# teensyShield4_1b.net
KiCad netlist of a schematic drawn in EAGLE
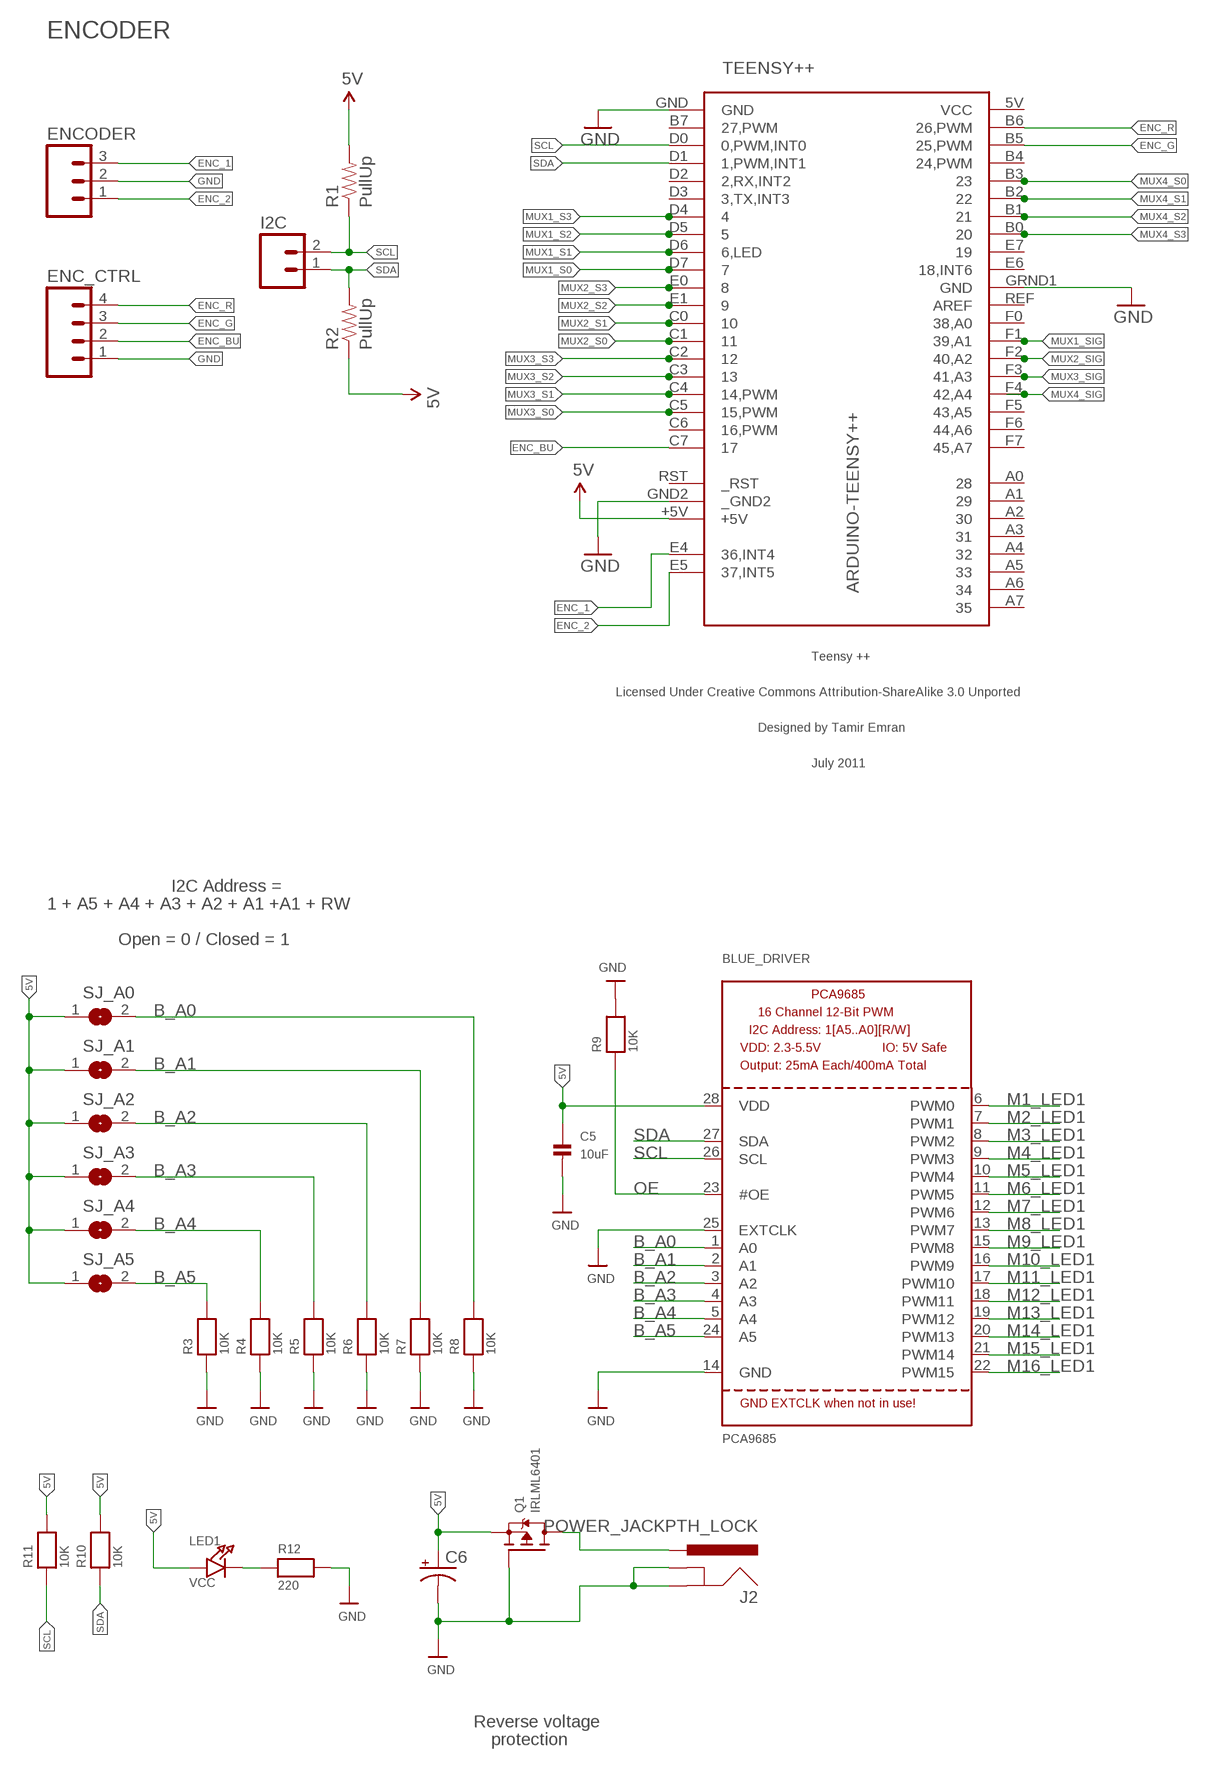
[diagram p0: schematic, sheet 1, part 1 of 2]
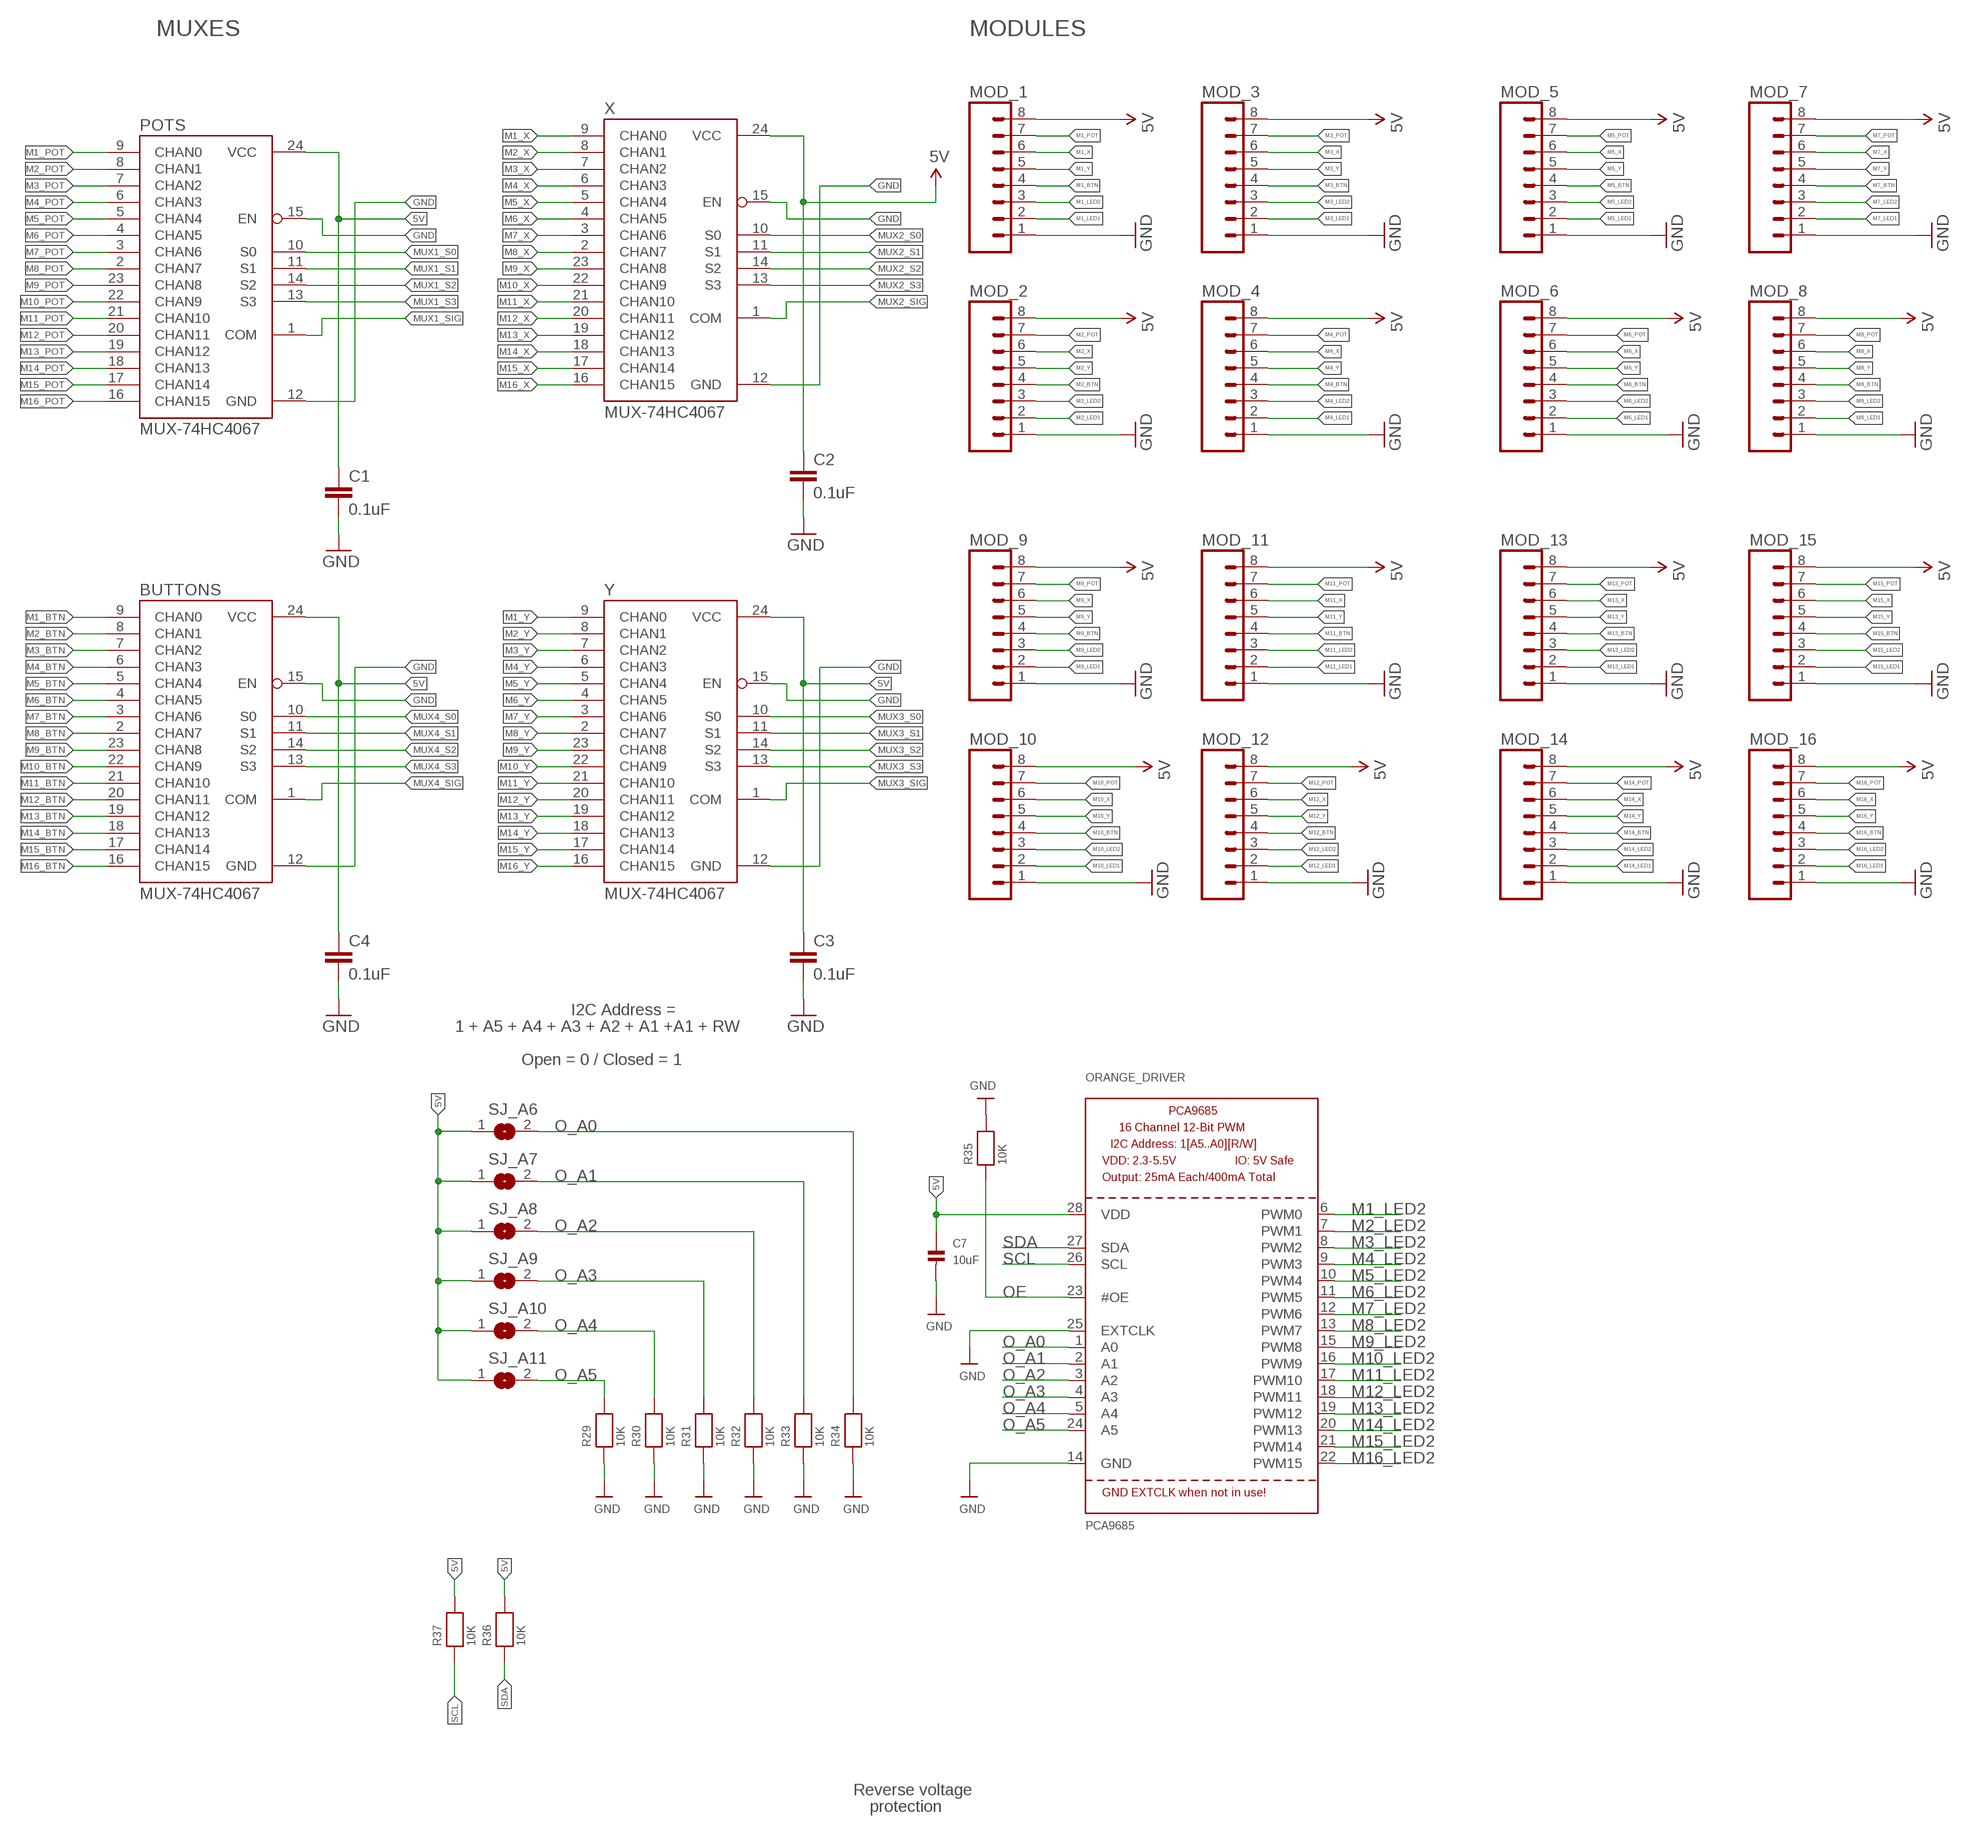
[diagram p1: schematic, sheet 1, part 2 of 2]

(export (version "E")
  (design (tool "Eeschema 10.0.6"))
  (components
    (comp (ref "BLUE_DRIVER")
      (value "PCA9685")
      (footprint "eagle-import:TSSOP28")
      (libsource (lib "eagle-import") (part "PCA9685"))
    )
    (comp (ref "BUTTONS")
      (value "MUX-74HC4067")
      (footprint "eagle-import:SSOP24")
      (libsource (lib "eagle-import") (part "MUX-74HC4067SMD"))
    )
    (comp (ref "C1")
      (value "0.1uF")
      (footprint "eagle-import:0603")
      (libsource (lib "eagle-import") (part "CAP0603"))
    )
    (comp (ref "C2")
      (value "0.1uF")
      (footprint "eagle-import:0603")
      (libsource (lib "eagle-import") (part "CAP0603"))
    )
    (comp (ref "C3")
      (value "0.1uF")
      (footprint "eagle-import:0603")
      (libsource (lib "eagle-import") (part "CAP0603"))
    )
    (comp (ref "C4")
      (value "0.1uF")
      (footprint "eagle-import:0603")
      (libsource (lib "eagle-import") (part "CAP0603"))
    )
    (comp (ref "C5")
      (value "10uF")
      (footprint "eagle-import:0805")
      (libsource (lib "eagle-import") (part "CAP_CERAMIC0805"))
    )
    (comp (ref "C6")
      (value "CPOL-USE3.5-8")
      (footprint "eagle-import:E3,5-8")
      (libsource (lib "eagle-import") (part "CPOL-USE3.5-8"))
    )
    (comp (ref "C7")
      (value "10uF")
      (footprint "eagle-import:0805")
      (libsource (lib "eagle-import") (part "CAP_CERAMIC0805"))
    )
    (comp (ref "ENCODER")
      (value "M031X03_NO_SILK")
      (footprint "eagle-import:1X03_NO_SILK")
      (libsource (lib "eagle-import") (part "M031X03_NO_SILK"))
    )
    (comp (ref "ENC_CTRL")
      (value "M041X04_NO_SILK")
      (footprint "eagle-import:1X04_NO_SILK")
      (libsource (lib "eagle-import") (part "M041X04_NO_SILK"))
    )
    (comp (ref "I2C")
      (value "M02LOCK")
      (footprint "eagle-import:1X02_LOCK")
      (libsource (lib "eagle-import") (part "M02LOCK"))
    )
    (comp (ref "J2")
      (value "POWER_JACKPTH_LOCK")
      (footprint "eagle-import:POWER_JACK_PTH_LOCK")
      (libsource (lib "eagle-import") (part "POWER_JACKPTH_LOCK"))
    )
    (comp (ref "LED1")
      (value "VCC")
      (footprint "eagle-import:CHIPLED_0805")
      (libsource (lib "eagle-import") (part "LED0805"))
    )
    (comp (ref "MOD_1")
      (value "M08")
      (footprint "eagle-import:1X08_ROUND")
      (libsource (lib "eagle-import") (part "M08"))
    )
    (comp (ref "MOD_2")
      (value "M08")
      (footprint "eagle-import:1X08_ROUND")
      (libsource (lib "eagle-import") (part "M08"))
    )
    (comp (ref "MOD_3")
      (value "M08")
      (footprint "eagle-import:1X08_ROUND")
      (libsource (lib "eagle-import") (part "M08"))
    )
    (comp (ref "MOD_4")
      (value "M08")
      (footprint "eagle-import:1X08_ROUND")
      (libsource (lib "eagle-import") (part "M08"))
    )
    (comp (ref "MOD_5")
      (value "M08")
      (footprint "eagle-import:1X08_ROUND")
      (libsource (lib "eagle-import") (part "M08"))
    )
    (comp (ref "MOD_6")
      (value "M08")
      (footprint "eagle-import:1X08_ROUND")
      (libsource (lib "eagle-import") (part "M08"))
    )
    (comp (ref "MOD_7")
      (value "M08")
      (footprint "eagle-import:1X08_ROUND")
      (libsource (lib "eagle-import") (part "M08"))
    )
    (comp (ref "MOD_8")
      (value "M08")
      (footprint "eagle-import:1X08_ROUND")
      (libsource (lib "eagle-import") (part "M08"))
    )
    (comp (ref "MOD_9")
      (value "M08")
      (footprint "eagle-import:1X08_ROUND")
      (libsource (lib "eagle-import") (part "M08"))
    )
    (comp (ref "MOD_10")
      (value "M08")
      (footprint "eagle-import:1X08_ROUND")
      (libsource (lib "eagle-import") (part "M08"))
    )
    (comp (ref "MOD_11")
      (value "M08")
      (footprint "eagle-import:1X08_ROUND")
      (libsource (lib "eagle-import") (part "M08"))
    )
    (comp (ref "MOD_12")
      (value "M08")
      (footprint "eagle-import:1X08_ROUND")
      (libsource (lib "eagle-import") (part "M08"))
    )
    (comp (ref "MOD_13")
      (value "M08")
      (footprint "eagle-import:1X08_ROUND")
      (libsource (lib "eagle-import") (part "M08"))
    )
    (comp (ref "MOD_14")
      (value "M08")
      (footprint "eagle-import:1X08_ROUND")
      (libsource (lib "eagle-import") (part "M08"))
    )
    (comp (ref "MOD_15")
      (value "M08")
      (footprint "eagle-import:1X08_ROUND")
      (libsource (lib "eagle-import") (part "M08"))
    )
    (comp (ref "MOD_16")
      (value "M08")
      (footprint "eagle-import:1X08_ROUND")
      (libsource (lib "eagle-import") (part "M08"))
    )
    (comp (ref "ORANGE_DRIVER")
      (value "PCA9685")
      (footprint "eagle-import:TSSOP28")
      (libsource (lib "eagle-import") (part "PCA9685"))
    )
    (comp (ref "POTS")
      (value "MUX-74HC4067")
      (footprint "eagle-import:SSOP24")
      (libsource (lib "eagle-import") (part "MUX-74HC4067SMD"))
    )
    (comp (ref "Q1")
      (value "IRLML6401")
      (footprint "eagle-import:SOT23-WIDE")
      (libsource (lib "eagle-import") (part "MOSFET-PWIDE"))
    )
    (comp (ref "R1")
      (value "PullUp")
      (footprint "eagle-import:AXIAL-0.3")
      (libsource (lib "eagle-import") (part "10KOHM-1/4W5%(PTH)"))
    )
    (comp (ref "R2")
      (value "PullUp")
      (footprint "eagle-import:AXIAL-0.3")
      (libsource (lib "eagle-import") (part "10KOHM-1/4W5%(PTH)"))
    )
    (comp (ref "R3")
      (value "10K")
      (footprint "eagle-import:0805")
      (libsource (lib "eagle-import") (part "RESISTOR0805"))
    )
    (comp (ref "R4")
      (value "10K")
      (footprint "eagle-import:0805")
      (libsource (lib "eagle-import") (part "RESISTOR0805"))
    )
    (comp (ref "R5")
      (value "10K")
      (footprint "eagle-import:0805")
      (libsource (lib "eagle-import") (part "RESISTOR0805"))
    )
    (comp (ref "R6")
      (value "10K")
      (footprint "eagle-import:0805")
      (libsource (lib "eagle-import") (part "RESISTOR0805"))
    )
    (comp (ref "R7")
      (value "10K")
      (footprint "eagle-import:0805")
      (libsource (lib "eagle-import") (part "RESISTOR0805"))
    )
    (comp (ref "R8")
      (value "10K")
      (footprint "eagle-import:0805")
      (libsource (lib "eagle-import") (part "RESISTOR0805"))
    )
    (comp (ref "R9")
      (value "10K")
      (footprint "eagle-import:0805")
      (libsource (lib "eagle-import") (part "RESISTOR0805"))
    )
    (comp (ref "R10")
      (value "10K")
      (footprint "eagle-import:0805")
      (libsource (lib "eagle-import") (part "RESISTOR0805"))
    )
    (comp (ref "R11")
      (value "10K")
      (footprint "eagle-import:0805")
      (libsource (lib "eagle-import") (part "RESISTOR0805"))
    )
    (comp (ref "R12")
      (value "220")
      (footprint "eagle-import:0805")
      (libsource (lib "eagle-import") (part "RESISTOR0805"))
    )
    (comp (ref "R29")
      (value "10K")
      (footprint "eagle-import:0805")
      (libsource (lib "eagle-import") (part "RESISTOR0805"))
    )
    (comp (ref "R30")
      (value "10K")
      (footprint "eagle-import:0805")
      (libsource (lib "eagle-import") (part "RESISTOR0805"))
    )
    (comp (ref "R31")
      (value "10K")
      (footprint "eagle-import:0805")
      (libsource (lib "eagle-import") (part "RESISTOR0805"))
    )
    (comp (ref "R32")
      (value "10K")
      (footprint "eagle-import:0805")
      (libsource (lib "eagle-import") (part "RESISTOR0805"))
    )
    (comp (ref "R33")
      (value "10K")
      (footprint "eagle-import:0805")
      (libsource (lib "eagle-import") (part "RESISTOR0805"))
    )
    (comp (ref "R34")
      (value "10K")
      (footprint "eagle-import:0805")
      (libsource (lib "eagle-import") (part "RESISTOR0805"))
    )
    (comp (ref "R35")
      (value "10K")
      (footprint "eagle-import:0805")
      (libsource (lib "eagle-import") (part "RESISTOR0805"))
    )
    (comp (ref "R36")
      (value "10K")
      (footprint "eagle-import:0805")
      (libsource (lib "eagle-import") (part "RESISTOR0805"))
    )
    (comp (ref "R37")
      (value "10K")
      (footprint "eagle-import:0805")
      (libsource (lib "eagle-import") (part "RESISTOR0805"))
    )
    (comp (ref "SJ_A0")
      (value "SOLDERJUMPERREFLOW_NOPASTE")
      (footprint "eagle-import:SOLDERJUMPER_REFLOW_NOPASTE")
      (libsource (lib "eagle-import") (part "SOLDERJUMPERREFLOW_NOPASTE"))
    )
    (comp (ref "SJ_A1")
      (value "SOLDERJUMPERREFLOW_NOPASTE")
      (footprint "eagle-import:SOLDERJUMPER_REFLOW_NOPASTE")
      (libsource (lib "eagle-import") (part "SOLDERJUMPERREFLOW_NOPASTE"))
    )
    (comp (ref "SJ_A2")
      (value "SOLDERJUMPERREFLOW_NOPASTE")
      (footprint "eagle-import:SOLDERJUMPER_REFLOW_NOPASTE")
      (libsource (lib "eagle-import") (part "SOLDERJUMPERREFLOW_NOPASTE"))
    )
    (comp (ref "SJ_A3")
      (value "SOLDERJUMPERREFLOW_NOPASTE")
      (footprint "eagle-import:SOLDERJUMPER_REFLOW_NOPASTE")
      (libsource (lib "eagle-import") (part "SOLDERJUMPERREFLOW_NOPASTE"))
    )
    (comp (ref "SJ_A4")
      (value "SOLDERJUMPERREFLOW_NOPASTE")
      (footprint "eagle-import:SOLDERJUMPER_REFLOW_NOPASTE")
      (libsource (lib "eagle-import") (part "SOLDERJUMPERREFLOW_NOPASTE"))
    )
    (comp (ref "SJ_A5")
      (value "SOLDERJUMPERREFLOW_NOPASTE")
      (footprint "eagle-import:SOLDERJUMPER_REFLOW_NOPASTE")
      (libsource (lib "eagle-import") (part "SOLDERJUMPERREFLOW_NOPASTE"))
    )
    (comp (ref "SJ_A6")
      (value "SOLDERJUMPERREFLOW_NOPASTE")
      (footprint "eagle-import:SOLDERJUMPER_REFLOW_NOPASTE")
      (libsource (lib "eagle-import") (part "SOLDERJUMPERREFLOW_NOPASTE"))
    )
    (comp (ref "SJ_A7")
      (value "SOLDERJUMPERREFLOW_NOPASTE")
      (footprint "eagle-import:SOLDERJUMPER_REFLOW_NOPASTE")
      (libsource (lib "eagle-import") (part "SOLDERJUMPERREFLOW_NOPASTE"))
    )
    (comp (ref "SJ_A8")
      (value "SOLDERJUMPERREFLOW_NOPASTE")
      (footprint "eagle-import:SOLDERJUMPER_REFLOW_NOPASTE")
      (libsource (lib "eagle-import") (part "SOLDERJUMPERREFLOW_NOPASTE"))
    )
    (comp (ref "SJ_A9")
      (value "SOLDERJUMPERREFLOW_NOPASTE")
      (footprint "eagle-import:SOLDERJUMPER_REFLOW_NOPASTE")
      (libsource (lib "eagle-import") (part "SOLDERJUMPERREFLOW_NOPASTE"))
    )
    (comp (ref "SJ_A10")
      (value "SOLDERJUMPERREFLOW_NOPASTE")
      (footprint "eagle-import:SOLDERJUMPER_REFLOW_NOPASTE")
      (libsource (lib "eagle-import") (part "SOLDERJUMPERREFLOW_NOPASTE"))
    )
    (comp (ref "SJ_A11")
      (value "SOLDERJUMPERREFLOW_NOPASTE")
      (footprint "eagle-import:SOLDERJUMPER_REFLOW_NOPASTE")
      (libsource (lib "eagle-import") (part "SOLDERJUMPERREFLOW_NOPASTE"))
    )
    (comp (ref "TEENSY++")
      (value "ARDUINO-TEENSY++")
      (footprint "eagle-import:TEENSY++")
      (libsource (lib "eagle-import") (part "ARDUINO-TEENSY++"))
    )
    (comp (ref "X")
      (value "MUX-74HC4067")
      (footprint "eagle-import:SSOP24")
      (libsource (lib "eagle-import") (part "MUX-74HC4067SMD"))
    )
    (comp (ref "Y")
      (value "MUX-74HC4067")
      (footprint "eagle-import:SSOP24")
      (libsource (lib "eagle-import") (part "MUX-74HC4067SMD"))
    )
  )
  (nets
    (net (code "1") (name "/B_A0") (class "Default")
      (node (ref "BLUE_DRIVER") (pin "1") (pinfunction "A0_1") (pintype "bidirectional"))
      (node (ref "R8") (pin "2") (pinfunction "2_2") (pintype "passive"))
      (node (ref "SJ_A0") (pin "2") (pinfunction "2_2") (pintype "passive"))
    )
    (net (code "2") (name "/B_A1") (class "Default")
      (node (ref "BLUE_DRIVER") (pin "2") (pinfunction "A1_2") (pintype "bidirectional"))
      (node (ref "R7") (pin "2") (pinfunction "2_2") (pintype "passive"))
      (node (ref "SJ_A1") (pin "2") (pinfunction "2_2") (pintype "passive"))
    )
    (net (code "3") (name "/B_A2") (class "Default")
      (node (ref "BLUE_DRIVER") (pin "3") (pinfunction "A2_3") (pintype "bidirectional"))
      (node (ref "R6") (pin "2") (pinfunction "2_2") (pintype "passive"))
      (node (ref "SJ_A2") (pin "2") (pinfunction "2_2") (pintype "passive"))
    )
    (net (code "4") (name "/B_A3") (class "Default")
      (node (ref "BLUE_DRIVER") (pin "4") (pinfunction "A3_4") (pintype "bidirectional"))
      (node (ref "R5") (pin "2") (pinfunction "2_2") (pintype "passive"))
      (node (ref "SJ_A3") (pin "2") (pinfunction "2_2") (pintype "passive"))
    )
    (net (code "5") (name "/B_A4") (class "Default")
      (node (ref "BLUE_DRIVER") (pin "5") (pinfunction "A4_5") (pintype "bidirectional"))
      (node (ref "R4") (pin "2") (pinfunction "2_2") (pintype "passive"))
      (node (ref "SJ_A4") (pin "2") (pinfunction "2_2") (pintype "passive"))
    )
    (net (code "6") (name "/B_A5") (class "Default")
      (node (ref "BLUE_DRIVER") (pin "24") (pinfunction "A5_24") (pintype "bidirectional"))
      (node (ref "R3") (pin "2") (pinfunction "2_2") (pintype "passive"))
      (node (ref "SJ_A5") (pin "2") (pinfunction "2_2") (pintype "passive"))
    )
    (net (code "7") (name "/OE") (class "Default")
      (node (ref "BLUE_DRIVER") (pin "23") (pinfunction "#OE_23") (pintype "input"))
      (node (ref "ORANGE_DRIVER") (pin "23") (pinfunction "#OE_23") (pintype "input"))
      (node (ref "R35") (pin "1") (pinfunction "1_1") (pintype "passive"))
      (node (ref "R9") (pin "1") (pinfunction "1_1") (pintype "passive"))
    )
    (net (code "8") (name "/O_A0") (class "Default")
      (node (ref "ORANGE_DRIVER") (pin "1") (pinfunction "A0_1") (pintype "bidirectional"))
      (node (ref "R34") (pin "2") (pinfunction "2_2") (pintype "passive"))
      (node (ref "SJ_A6") (pin "2") (pinfunction "2_2") (pintype "passive"))
    )
    (net (code "9") (name "/O_A1") (class "Default")
      (node (ref "ORANGE_DRIVER") (pin "2") (pinfunction "A1_2") (pintype "bidirectional"))
      (node (ref "R33") (pin "2") (pinfunction "2_2") (pintype "passive"))
      (node (ref "SJ_A7") (pin "2") (pinfunction "2_2") (pintype "passive"))
    )
    (net (code "10") (name "/O_A2") (class "Default")
      (node (ref "ORANGE_DRIVER") (pin "3") (pinfunction "A2_3") (pintype "bidirectional"))
      (node (ref "R32") (pin "2") (pinfunction "2_2") (pintype "passive"))
      (node (ref "SJ_A8") (pin "2") (pinfunction "2_2") (pintype "passive"))
    )
    (net (code "11") (name "/O_A3") (class "Default")
      (node (ref "ORANGE_DRIVER") (pin "4") (pinfunction "A3_4") (pintype "bidirectional"))
      (node (ref "R31") (pin "2") (pinfunction "2_2") (pintype "passive"))
      (node (ref "SJ_A9") (pin "2") (pinfunction "2_2") (pintype "passive"))
    )
    (net (code "12") (name "/O_A4") (class "Default")
      (node (ref "ORANGE_DRIVER") (pin "5") (pinfunction "A4_5") (pintype "bidirectional"))
      (node (ref "R30") (pin "2") (pinfunction "2_2") (pintype "passive"))
      (node (ref "SJ_A10") (pin "2") (pinfunction "2_2") (pintype "passive"))
    )
    (net (code "13") (name "/O_A5") (class "Default")
      (node (ref "ORANGE_DRIVER") (pin "24") (pinfunction "A5_24") (pintype "bidirectional"))
      (node (ref "R29") (pin "2") (pinfunction "2_2") (pintype "passive"))
      (node (ref "SJ_A11") (pin "2") (pinfunction "2_2") (pintype "passive"))
    )
    (net (code "14") (name "/VCC") (class "Default")
      (node (ref "TEENSY++") (pin "5V") (pinfunction "VCC_5V") (pintype "power_in"))
    )
    (net (code "15") (name "5V") (class "Default")
      (node (ref "BLUE_DRIVER") (pin "28") (pinfunction "VDD_28") (pintype "power_in"))
      (node (ref "BUTTONS") (pin "24") (pinfunction "VCC_24") (pintype "bidirectional"))
      (node (ref "C1") (pin "1") (pinfunction "1_1") (pintype "passive"))
      (node (ref "C2") (pin "1") (pinfunction "1_1") (pintype "passive"))
      (node (ref "C3") (pin "1") (pinfunction "1_1") (pintype "passive"))
      (node (ref "C4") (pin "1") (pinfunction "1_1") (pintype "passive"))
      (node (ref "C5") (pin "1") (pinfunction "P$1_1") (pintype "passive"))
      (node (ref "C6") (pin "+") (pinfunction "+_+") (pintype "passive"))
      (node (ref "C7") (pin "1") (pinfunction "P$1_1") (pintype "passive"))
      (node (ref "LED1") (pin "A") (pinfunction "A_A") (pintype "passive"))
      (node (ref "MOD_1") (pin "8") (pinfunction "8_8") (pintype "passive"))
      (node (ref "MOD_10") (pin "8") (pinfunction "8_8") (pintype "passive"))
      (node (ref "MOD_11") (pin "8") (pinfunction "8_8") (pintype "passive"))
      (node (ref "MOD_12") (pin "8") (pinfunction "8_8") (pintype "passive"))
      (node (ref "MOD_13") (pin "8") (pinfunction "8_8") (pintype "passive"))
      (node (ref "MOD_14") (pin "8") (pinfunction "8_8") (pintype "passive"))
      (node (ref "MOD_15") (pin "8") (pinfunction "8_8") (pintype "passive"))
      (node (ref "MOD_16") (pin "8") (pinfunction "8_8") (pintype "passive"))
      (node (ref "MOD_2") (pin "8") (pinfunction "8_8") (pintype "passive"))
      (node (ref "MOD_3") (pin "8") (pinfunction "8_8") (pintype "passive"))
      (node (ref "MOD_4") (pin "8") (pinfunction "8_8") (pintype "passive"))
      (node (ref "MOD_5") (pin "8") (pinfunction "8_8") (pintype "passive"))
      (node (ref "MOD_6") (pin "8") (pinfunction "8_8") (pintype "passive"))
      (node (ref "MOD_7") (pin "8") (pinfunction "8_8") (pintype "passive"))
      (node (ref "MOD_8") (pin "8") (pinfunction "8_8") (pintype "passive"))
      (node (ref "MOD_9") (pin "8") (pinfunction "8_8") (pintype "passive"))
      (node (ref "ORANGE_DRIVER") (pin "28") (pinfunction "VDD_28") (pintype "power_in"))
      (node (ref "POTS") (pin "24") (pinfunction "VCC_24") (pintype "bidirectional"))
      (node (ref "Q1") (pin "2") (pinfunction "S_2") (pintype "passive"))
      (node (ref "R1") (pin "P$2") (pinfunction "2_P$2") (pintype "passive"))
      (node (ref "R10") (pin "2") (pinfunction "2_2") (pintype "passive"))
      (node (ref "R11") (pin "2") (pinfunction "2_2") (pintype "passive"))
      (node (ref "R2") (pin "P$1") (pinfunction "1_P$1") (pintype "passive"))
      (node (ref "R36") (pin "2") (pinfunction "2_2") (pintype "passive"))
      (node (ref "R37") (pin "2") (pinfunction "2_2") (pintype "passive"))
      (node (ref "SJ_A0") (pin "1") (pinfunction "1_1") (pintype "passive"))
      (node (ref "SJ_A1") (pin "1") (pinfunction "1_1") (pintype "passive"))
      (node (ref "SJ_A10") (pin "1") (pinfunction "1_1") (pintype "passive"))
      (node (ref "SJ_A11") (pin "1") (pinfunction "1_1") (pintype "passive"))
      (node (ref "SJ_A2") (pin "1") (pinfunction "1_1") (pintype "passive"))
      (node (ref "SJ_A3") (pin "1") (pinfunction "1_1") (pintype "passive"))
      (node (ref "SJ_A4") (pin "1") (pinfunction "1_1") (pintype "passive"))
      (node (ref "SJ_A5") (pin "1") (pinfunction "1_1") (pintype "passive"))
      (node (ref "SJ_A6") (pin "1") (pinfunction "1_1") (pintype "passive"))
      (node (ref "SJ_A7") (pin "1") (pinfunction "1_1") (pintype "passive"))
      (node (ref "SJ_A8") (pin "1") (pinfunction "1_1") (pintype "passive"))
      (node (ref "SJ_A9") (pin "1") (pinfunction "1_1") (pintype "passive"))
      (node (ref "TEENSY++") (pin "+5V") (pinfunction "+5V_+5V") (pintype "power_in"))
      (node (ref "X") (pin "24") (pinfunction "VCC_24") (pintype "bidirectional"))
      (node (ref "Y") (pin "24") (pinfunction "VCC_24") (pintype "bidirectional"))
    )
    (net (code "16") (name "ENC_1") (class "Default")
      (node (ref "ENCODER") (pin "3") (pinfunction "3_3") (pintype "passive"))
      (node (ref "TEENSY++") (pin "E4") (pinfunction "36,INT4_E4") (pintype "bidirectional"))
    )
    (net (code "17") (name "ENC_2") (class "Default")
      (node (ref "ENCODER") (pin "1") (pinfunction "1_1") (pintype "passive"))
      (node (ref "TEENSY++") (pin "E5") (pinfunction "37,INT5_E5") (pintype "bidirectional"))
    )
    (net (code "18") (name "ENC_BU") (class "Default")
      (node (ref "ENC_CTRL") (pin "2") (pinfunction "2_2") (pintype "passive"))
      (node (ref "TEENSY++") (pin "C7") (pinfunction "17_C7") (pintype "bidirectional"))
    )
    (net (code "19") (name "ENC_G") (class "Default")
      (node (ref "ENC_CTRL") (pin "3") (pinfunction "3_3") (pintype "passive"))
      (node (ref "TEENSY++") (pin "B5") (pinfunction "25,PWM_B5") (pintype "bidirectional"))
    )
    (net (code "20") (name "ENC_R") (class "Default")
      (node (ref "ENC_CTRL") (pin "4") (pinfunction "4_4") (pintype "passive"))
      (node (ref "TEENSY++") (pin "B6") (pinfunction "26,PWM_B6") (pintype "bidirectional"))
    )
    (net (code "21") (name "GND") (class "Default")
      (node (ref "BLUE_DRIVER") (pin "14") (pinfunction "GND_14") (pintype "power_in"))
      (node (ref "BLUE_DRIVER") (pin "25") (pinfunction "EXTCLK_25") (pintype "input"))
      (node (ref "BUTTONS") (pin "12") (pinfunction "GND_12") (pintype "bidirectional"))
      (node (ref "BUTTONS") (pin "15") (pinfunction "EN_15") (pintype "input"))
      (node (ref "C1") (pin "2") (pinfunction "2_2") (pintype "passive"))
      (node (ref "C2") (pin "2") (pinfunction "2_2") (pintype "passive"))
      (node (ref "C3") (pin "2") (pinfunction "2_2") (pintype "passive"))
      (node (ref "C4") (pin "2") (pinfunction "2_2") (pintype "passive"))
      (node (ref "C5") (pin "2") (pinfunction "P$2_2") (pintype "passive"))
      (node (ref "C6") (pin "-") (pinfunction "-_-") (pintype "passive"))
      (node (ref "C7") (pin "2") (pinfunction "P$2_2") (pintype "passive"))
      (node (ref "ENCODER") (pin "2") (pinfunction "2_2") (pintype "passive"))
      (node (ref "ENC_CTRL") (pin "1") (pinfunction "1_1") (pintype "passive"))
      (node (ref "J2") (pin "GND") (pinfunction "GND_GND") (pintype "bidirectional"))
      (node (ref "J2") (pin "GNDBREAK") (pinfunction "GNDBREAK_GNDBREAK") (pintype "bidirectional"))
      (node (ref "MOD_1") (pin "1") (pinfunction "1_1") (pintype "passive"))
      (node (ref "MOD_10") (pin "1") (pinfunction "1_1") (pintype "passive"))
      (node (ref "MOD_11") (pin "1") (pinfunction "1_1") (pintype "passive"))
      (node (ref "MOD_12") (pin "1") (pinfunction "1_1") (pintype "passive"))
      (node (ref "MOD_13") (pin "1") (pinfunction "1_1") (pintype "passive"))
      (node (ref "MOD_14") (pin "1") (pinfunction "1_1") (pintype "passive"))
      (node (ref "MOD_15") (pin "1") (pinfunction "1_1") (pintype "passive"))
      (node (ref "MOD_16") (pin "1") (pinfunction "1_1") (pintype "passive"))
      (node (ref "MOD_2") (pin "1") (pinfunction "1_1") (pintype "passive"))
      (node (ref "MOD_3") (pin "1") (pinfunction "1_1") (pintype "passive"))
      (node (ref "MOD_4") (pin "1") (pinfunction "1_1") (pintype "passive"))
      (node (ref "MOD_5") (pin "1") (pinfunction "1_1") (pintype "passive"))
      (node (ref "MOD_6") (pin "1") (pinfunction "1_1") (pintype "passive"))
      (node (ref "MOD_7") (pin "1") (pinfunction "1_1") (pintype "passive"))
      (node (ref "MOD_8") (pin "1") (pinfunction "1_1") (pintype "passive"))
      (node (ref "MOD_9") (pin "1") (pinfunction "1_1") (pintype "passive"))
      (node (ref "ORANGE_DRIVER") (pin "14") (pinfunction "GND_14") (pintype "power_in"))
      (node (ref "ORANGE_DRIVER") (pin "25") (pinfunction "EXTCLK_25") (pintype "input"))
      (node (ref "POTS") (pin "12") (pinfunction "GND_12") (pintype "bidirectional"))
      (node (ref "POTS") (pin "15") (pinfunction "EN_15") (pintype "input"))
      (node (ref "Q1") (pin "1") (pinfunction "G_1") (pintype "passive"))
      (node (ref "R12") (pin "2") (pinfunction "2_2") (pintype "passive"))
      (node (ref "R29") (pin "1") (pinfunction "1_1") (pintype "passive"))
      (node (ref "R3") (pin "1") (pinfunction "1_1") (pintype "passive"))
      (node (ref "R30") (pin "1") (pinfunction "1_1") (pintype "passive"))
      (node (ref "R31") (pin "1") (pinfunction "1_1") (pintype "passive"))
      (node (ref "R32") (pin "1") (pinfunction "1_1") (pintype "passive"))
      (node (ref "R33") (pin "1") (pinfunction "1_1") (pintype "passive"))
      (node (ref "R34") (pin "1") (pinfunction "1_1") (pintype "passive"))
      (node (ref "R35") (pin "2") (pinfunction "2_2") (pintype "passive"))
      (node (ref "R4") (pin "1") (pinfunction "1_1") (pintype "passive"))
      (node (ref "R5") (pin "1") (pinfunction "1_1") (pintype "passive"))
      (node (ref "R6") (pin "1") (pinfunction "1_1") (pintype "passive"))
      (node (ref "R7") (pin "1") (pinfunction "1_1") (pintype "passive"))
      (node (ref "R8") (pin "1") (pinfunction "1_1") (pintype "passive"))
      (node (ref "R9") (pin "2") (pinfunction "2_2") (pintype "passive"))
      (node (ref "TEENSY++") (pin "GND") (pinfunction "GND_GND") (pintype "power_in"))
      (node (ref "TEENSY++") (pin "GND2") (pinfunction "_GND2_GND2") (pintype "power_in"))
      (node (ref "TEENSY++") (pin "GRND1") (pinfunction "GND_GRND1") (pintype "power_in"))
      (node (ref "X") (pin "12") (pinfunction "GND_12") (pintype "bidirectional"))
      (node (ref "X") (pin "15") (pinfunction "EN_15") (pintype "input"))
      (node (ref "Y") (pin "12") (pinfunction "GND_12") (pintype "bidirectional"))
      (node (ref "Y") (pin "15") (pinfunction "EN_15") (pintype "input"))
    )
    (net (code "22") (name "M1_BTN") (class "Default")
      (node (ref "BUTTONS") (pin "9") (pinfunction "CHAN0_9") (pintype "bidirectional"))
      (node (ref "MOD_1") (pin "4") (pinfunction "4_4") (pintype "passive"))
    )
    (net (code "23") (name "M1_LED1") (class "Default")
      (node (ref "BLUE_DRIVER") (pin "6") (pinfunction "PWM0_6") (pintype "output"))
      (node (ref "MOD_1") (pin "2") (pinfunction "2_2") (pintype "passive"))
    )
    (net (code "24") (name "M1_LED2") (class "Default")
      (node (ref "MOD_1") (pin "3") (pinfunction "3_3") (pintype "passive"))
      (node (ref "ORANGE_DRIVER") (pin "6") (pinfunction "PWM0_6") (pintype "output"))
    )
    (net (code "25") (name "M1_POT") (class "Default")
      (node (ref "MOD_1") (pin "7") (pinfunction "7_7") (pintype "passive"))
      (node (ref "POTS") (pin "9") (pinfunction "CHAN0_9") (pintype "bidirectional"))
    )
    (net (code "26") (name "M1_X") (class "Default")
      (node (ref "MOD_1") (pin "6") (pinfunction "6_6") (pintype "passive"))
      (node (ref "X") (pin "9") (pinfunction "CHAN0_9") (pintype "bidirectional"))
    )
    (net (code "27") (name "M1_Y") (class "Default")
      (node (ref "MOD_1") (pin "5") (pinfunction "5_5") (pintype "passive"))
      (node (ref "Y") (pin "9") (pinfunction "CHAN0_9") (pintype "bidirectional"))
    )
    (net (code "28") (name "M2_BTN") (class "Default")
      (node (ref "BUTTONS") (pin "8") (pinfunction "CHAN1_8") (pintype "bidirectional"))
      (node (ref "MOD_2") (pin "4") (pinfunction "4_4") (pintype "passive"))
    )
    (net (code "29") (name "M2_LED1") (class "Default")
      (node (ref "BLUE_DRIVER") (pin "7") (pinfunction "PWM1_7") (pintype "output"))
      (node (ref "MOD_2") (pin "2") (pinfunction "2_2") (pintype "passive"))
    )
    (net (code "30") (name "M2_LED2") (class "Default")
      (node (ref "MOD_2") (pin "3") (pinfunction "3_3") (pintype "passive"))
      (node (ref "ORANGE_DRIVER") (pin "7") (pinfunction "PWM1_7") (pintype "output"))
    )
    (net (code "31") (name "M2_POT") (class "Default")
      (node (ref "MOD_2") (pin "7") (pinfunction "7_7") (pintype "passive"))
      (node (ref "POTS") (pin "8") (pinfunction "CHAN1_8") (pintype "bidirectional"))
    )
    (net (code "32") (name "M2_X") (class "Default")
      (node (ref "MOD_2") (pin "6") (pinfunction "6_6") (pintype "passive"))
      (node (ref "X") (pin "8") (pinfunction "CHAN1_8") (pintype "bidirectional"))
    )
    (net (code "33") (name "M2_Y") (class "Default")
      (node (ref "MOD_2") (pin "5") (pinfunction "5_5") (pintype "passive"))
      (node (ref "Y") (pin "8") (pinfunction "CHAN1_8") (pintype "bidirectional"))
    )
    (net (code "34") (name "M3_BTN") (class "Default")
      (node (ref "BUTTONS") (pin "7") (pinfunction "CHAN2_7") (pintype "bidirectional"))
      (node (ref "MOD_3") (pin "4") (pinfunction "4_4") (pintype "passive"))
    )
    (net (code "35") (name "M3_LED1") (class "Default")
      (node (ref "BLUE_DRIVER") (pin "8") (pinfunction "PWM2_8") (pintype "output"))
      (node (ref "MOD_3") (pin "2") (pinfunction "2_2") (pintype "passive"))
    )
    (net (code "36") (name "M3_LED2") (class "Default")
      (node (ref "MOD_3") (pin "3") (pinfunction "3_3") (pintype "passive"))
      (node (ref "ORANGE_DRIVER") (pin "8") (pinfunction "PWM2_8") (pintype "output"))
    )
    (net (code "37") (name "M3_POT") (class "Default")
      (node (ref "MOD_3") (pin "7") (pinfunction "7_7") (pintype "passive"))
      (node (ref "POTS") (pin "7") (pinfunction "CHAN2_7") (pintype "bidirectional"))
    )
    (net (code "38") (name "M3_X") (class "Default")
      (node (ref "MOD_3") (pin "6") (pinfunction "6_6") (pintype "passive"))
      (node (ref "X") (pin "7") (pinfunction "CHAN2_7") (pintype "bidirectional"))
    )
    (net (code "39") (name "M3_Y") (class "Default")
      (node (ref "MOD_3") (pin "5") (pinfunction "5_5") (pintype "passive"))
      (node (ref "Y") (pin "7") (pinfunction "CHAN2_7") (pintype "bidirectional"))
    )
    (net (code "40") (name "M4_BTN") (class "Default")
      (node (ref "BUTTONS") (pin "6") (pinfunction "CHAN3_6") (pintype "bidirectional"))
      (node (ref "MOD_4") (pin "4") (pinfunction "4_4") (pintype "passive"))
    )
    (net (code "41") (name "M4_LED1") (class "Default")
      (node (ref "BLUE_DRIVER") (pin "9") (pinfunction "PWM3_9") (pintype "output"))
      (node (ref "MOD_4") (pin "2") (pinfunction "2_2") (pintype "passive"))
    )
    (net (code "42") (name "M4_LED2") (class "Default")
      (node (ref "MOD_4") (pin "3") (pinfunction "3_3") (pintype "passive"))
      (node (ref "ORANGE_DRIVER") (pin "9") (pinfunction "PWM3_9") (pintype "output"))
    )
    (net (code "43") (name "M4_POT") (class "Default")
      (node (ref "MOD_4") (pin "7") (pinfunction "7_7") (pintype "passive"))
      (node (ref "POTS") (pin "6") (pinfunction "CHAN3_6") (pintype "bidirectional"))
    )
    (net (code "44") (name "M4_X") (class "Default")
      (node (ref "MOD_4") (pin "6") (pinfunction "6_6") (pintype "passive"))
      (node (ref "X") (pin "6") (pinfunction "CHAN3_6") (pintype "bidirectional"))
    )
    (net (code "45") (name "M4_Y") (class "Default")
      (node (ref "MOD_4") (pin "5") (pinfunction "5_5") (pintype "passive"))
      (node (ref "Y") (pin "6") (pinfunction "CHAN3_6") (pintype "bidirectional"))
    )
    (net (code "46") (name "M5_BTN") (class "Default")
      (node (ref "BUTTONS") (pin "5") (pinfunction "CHAN4_5") (pintype "bidirectional"))
      (node (ref "MOD_5") (pin "4") (pinfunction "4_4") (pintype "passive"))
    )
    (net (code "47") (name "M5_LED1") (class "Default")
      (node (ref "BLUE_DRIVER") (pin "10") (pinfunction "PWM4_10") (pintype "output"))
      (node (ref "MOD_5") (pin "2") (pinfunction "2_2") (pintype "passive"))
    )
    (net (code "48") (name "M5_LED2") (class "Default")
      (node (ref "MOD_5") (pin "3") (pinfunction "3_3") (pintype "passive"))
      (node (ref "ORANGE_DRIVER") (pin "10") (pinfunction "PWM4_10") (pintype "output"))
    )
    (net (code "49") (name "M5_POT") (class "Default")
      (node (ref "MOD_5") (pin "7") (pinfunction "7_7") (pintype "passive"))
      (node (ref "POTS") (pin "5") (pinfunction "CHAN4_5") (pintype "bidirectional"))
    )
    (net (code "50") (name "M5_X") (class "Default")
      (node (ref "MOD_5") (pin "6") (pinfunction "6_6") (pintype "passive"))
      (node (ref "X") (pin "5") (pinfunction "CHAN4_5") (pintype "bidirectional"))
    )
    (net (code "51") (name "M5_Y") (class "Default")
      (node (ref "MOD_5") (pin "5") (pinfunction "5_5") (pintype "passive"))
      (node (ref "Y") (pin "5") (pinfunction "CHAN4_5") (pintype "bidirectional"))
    )
    (net (code "52") (name "M6_BTN") (class "Default")
      (node (ref "BUTTONS") (pin "4") (pinfunction "CHAN5_4") (pintype "bidirectional"))
      (node (ref "MOD_6") (pin "4") (pinfunction "4_4") (pintype "passive"))
    )
    (net (code "53") (name "M6_LED1") (class "Default")
      (node (ref "BLUE_DRIVER") (pin "11") (pinfunction "PWM5_11") (pintype "output"))
      (node (ref "MOD_6") (pin "2") (pinfunction "2_2") (pintype "passive"))
    )
    (net (code "54") (name "M6_LED2") (class "Default")
      (node (ref "MOD_6") (pin "3") (pinfunction "3_3") (pintype "passive"))
      (node (ref "ORANGE_DRIVER") (pin "11") (pinfunction "PWM5_11") (pintype "output"))
    )
    (net (code "55") (name "M6_POT") (class "Default")
      (node (ref "MOD_6") (pin "7") (pinfunction "7_7") (pintype "passive"))
      (node (ref "POTS") (pin "4") (pinfunction "CHAN5_4") (pintype "bidirectional"))
    )
    (net (code "56") (name "M6_X") (class "Default")
      (node (ref "MOD_6") (pin "6") (pinfunction "6_6") (pintype "passive"))
      (node (ref "X") (pin "4") (pinfunction "CHAN5_4") (pintype "bidirectional"))
    )
    (net (code "57") (name "M6_Y") (class "Default")
      (node (ref "MOD_6") (pin "5") (pinfunction "5_5") (pintype "passive"))
      (node (ref "Y") (pin "4") (pinfunction "CHAN5_4") (pintype "bidirectional"))
    )
    (net (code "58") (name "M7_BTN") (class "Default")
      (node (ref "BUTTONS") (pin "3") (pinfunction "CHAN6_3") (pintype "bidirectional"))
      (node (ref "MOD_7") (pin "4") (pinfunction "4_4") (pintype "passive"))
    )
    (net (code "59") (name "M7_LED1") (class "Default")
      (node (ref "BLUE_DRIVER") (pin "12") (pinfunction "PWM6_12") (pintype "output"))
      (node (ref "MOD_7") (pin "2") (pinfunction "2_2") (pintype "passive"))
    )
    (net (code "60") (name "M7_LED2") (class "Default")
      (node (ref "MOD_7") (pin "3") (pinfunction "3_3") (pintype "passive"))
      (node (ref "ORANGE_DRIVER") (pin "12") (pinfunction "PWM6_12") (pintype "output"))
    )
    (net (code "61") (name "M7_POT") (class "Default")
      (node (ref "MOD_7") (pin "7") (pinfunction "7_7") (pintype "passive"))
      (node (ref "POTS") (pin "3") (pinfunction "CHAN6_3") (pintype "bidirectional"))
    )
    (net (code "62") (name "M7_X") (class "Default")
      (node (ref "MOD_7") (pin "6") (pinfunction "6_6") (pintype "passive"))
      (node (ref "X") (pin "3") (pinfunction "CHAN6_3") (pintype "bidirectional"))
    )
    (net (code "63") (name "M7_Y") (class "Default")
      (node (ref "MOD_7") (pin "5") (pinfunction "5_5") (pintype "passive"))
      (node (ref "Y") (pin "3") (pinfunction "CHAN6_3") (pintype "bidirectional"))
    )
    (net (code "64") (name "M8_BTN") (class "Default")
      (node (ref "BUTTONS") (pin "2") (pinfunction "CHAN7_2") (pintype "bidirectional"))
      (node (ref "MOD_8") (pin "4") (pinfunction "4_4") (pintype "passive"))
    )
    (net (code "65") (name "M8_LED1") (class "Default")
      (node (ref "BLUE_DRIVER") (pin "13") (pinfunction "PWM7_13") (pintype "output"))
      (node (ref "MOD_8") (pin "2") (pinfunction "2_2") (pintype "passive"))
    )
    (net (code "66") (name "M8_LED2") (class "Default")
      (node (ref "MOD_8") (pin "3") (pinfunction "3_3") (pintype "passive"))
      (node (ref "ORANGE_DRIVER") (pin "13") (pinfunction "PWM7_13") (pintype "output"))
    )
    (net (code "67") (name "M8_POT") (class "Default")
      (node (ref "MOD_8") (pin "7") (pinfunction "7_7") (pintype "passive"))
      (node (ref "POTS") (pin "2") (pinfunction "CHAN7_2") (pintype "bidirectional"))
    )
    (net (code "68") (name "M8_X") (class "Default")
      (node (ref "MOD_8") (pin "6") (pinfunction "6_6") (pintype "passive"))
      (node (ref "X") (pin "2") (pinfunction "CHAN7_2") (pintype "bidirectional"))
    )
    (net (code "69") (name "M8_Y") (class "Default")
      (node (ref "MOD_8") (pin "5") (pinfunction "5_5") (pintype "passive"))
      (node (ref "Y") (pin "2") (pinfunction "CHAN7_2") (pintype "bidirectional"))
    )
    (net (code "70") (name "M9_BTN") (class "Default")
      (node (ref "BUTTONS") (pin "23") (pinfunction "CHAN8_23") (pintype "bidirectional"))
      (node (ref "MOD_9") (pin "4") (pinfunction "4_4") (pintype "passive"))
    )
    (net (code "71") (name "M9_LED1") (class "Default")
      (node (ref "BLUE_DRIVER") (pin "15") (pinfunction "PWM8_15") (pintype "output"))
      (node (ref "MOD_9") (pin "2") (pinfunction "2_2") (pintype "passive"))
    )
    (net (code "72") (name "M9_LED2") (class "Default")
      (node (ref "MOD_9") (pin "3") (pinfunction "3_3") (pintype "passive"))
      (node (ref "ORANGE_DRIVER") (pin "15") (pinfunction "PWM8_15") (pintype "output"))
    )
    (net (code "73") (name "M9_POT") (class "Default")
      (node (ref "MOD_9") (pin "7") (pinfunction "7_7") (pintype "passive"))
      (node (ref "POTS") (pin "23") (pinfunction "CHAN8_23") (pintype "bidirectional"))
    )
    (net (code "74") (name "M9_X") (class "Default")
      (node (ref "MOD_9") (pin "6") (pinfunction "6_6") (pintype "passive"))
      (node (ref "X") (pin "23") (pinfunction "CHAN8_23") (pintype "bidirectional"))
    )
    (net (code "75") (name "M9_Y") (class "Default")
      (node (ref "MOD_9") (pin "5") (pinfunction "5_5") (pintype "passive"))
      (node (ref "Y") (pin "23") (pinfunction "CHAN8_23") (pintype "bidirectional"))
    )
    (net (code "76") (name "M10_BTN") (class "Default")
      (node (ref "BUTTONS") (pin "22") (pinfunction "CHAN9_22") (pintype "bidirectional"))
      (node (ref "MOD_10") (pin "4") (pinfunction "4_4") (pintype "passive"))
    )
    (net (code "77") (name "M10_LED1") (class "Default")
      (node (ref "BLUE_DRIVER") (pin "16") (pinfunction "PWM9_16") (pintype "output"))
      (node (ref "MOD_10") (pin "2") (pinfunction "2_2") (pintype "passive"))
    )
    (net (code "78") (name "M10_LED2") (class "Default")
      (node (ref "MOD_10") (pin "3") (pinfunction "3_3") (pintype "passive"))
      (node (ref "ORANGE_DRIVER") (pin "16") (pinfunction "PWM9_16") (pintype "output"))
    )
    (net (code "79") (name "M10_POT") (class "Default")
      (node (ref "MOD_10") (pin "7") (pinfunction "7_7") (pintype "passive"))
      (node (ref "POTS") (pin "22") (pinfunction "CHAN9_22") (pintype "bidirectional"))
    )
    (net (code "80") (name "M10_X") (class "Default")
      (node (ref "MOD_10") (pin "6") (pinfunction "6_6") (pintype "passive"))
      (node (ref "X") (pin "22") (pinfunction "CHAN9_22") (pintype "bidirectional"))
    )
    (net (code "81") (name "M10_Y") (class "Default")
      (node (ref "MOD_10") (pin "5") (pinfunction "5_5") (pintype "passive"))
      (node (ref "Y") (pin "22") (pinfunction "CHAN9_22") (pintype "bidirectional"))
    )
    (net (code "82") (name "M11_BTN") (class "Default")
      (node (ref "BUTTONS") (pin "21") (pinfunction "CHAN10_21") (pintype "bidirectional"))
      (node (ref "MOD_11") (pin "4") (pinfunction "4_4") (pintype "passive"))
    )
    (net (code "83") (name "M11_LED1") (class "Default")
      (node (ref "BLUE_DRIVER") (pin "17") (pinfunction "PWM10_17") (pintype "output"))
      (node (ref "MOD_11") (pin "2") (pinfunction "2_2") (pintype "passive"))
    )
    (net (code "84") (name "M11_LED2") (class "Default")
      (node (ref "MOD_11") (pin "3") (pinfunction "3_3") (pintype "passive"))
      (node (ref "ORANGE_DRIVER") (pin "17") (pinfunction "PWM10_17") (pintype "output"))
    )
    (net (code "85") (name "M11_POT") (class "Default")
      (node (ref "MOD_11") (pin "7") (pinfunction "7_7") (pintype "passive"))
      (node (ref "POTS") (pin "21") (pinfunction "CHAN10_21") (pintype "bidirectional"))
    )
    (net (code "86") (name "M11_X") (class "Default")
      (node (ref "MOD_11") (pin "6") (pinfunction "6_6") (pintype "passive"))
      (node (ref "X") (pin "21") (pinfunction "CHAN10_21") (pintype "bidirectional"))
    )
    (net (code "87") (name "M11_Y") (class "Default")
      (node (ref "MOD_11") (pin "5") (pinfunction "5_5") (pintype "passive"))
      (node (ref "Y") (pin "21") (pinfunction "CHAN10_21") (pintype "bidirectional"))
    )
    (net (code "88") (name "M12_BTN") (class "Default")
      (node (ref "BUTTONS") (pin "20") (pinfunction "CHAN11_20") (pintype "bidirectional"))
      (node (ref "MOD_12") (pin "4") (pinfunction "4_4") (pintype "passive"))
    )
    (net (code "89") (name "M12_LED1") (class "Default")
      (node (ref "BLUE_DRIVER") (pin "18") (pinfunction "PWM11_18") (pintype "output"))
      (node (ref "MOD_12") (pin "2") (pinfunction "2_2") (pintype "passive"))
    )
    (net (code "90") (name "M12_LED2") (class "Default")
      (node (ref "MOD_12") (pin "3") (pinfunction "3_3") (pintype "passive"))
      (node (ref "ORANGE_DRIVER") (pin "18") (pinfunction "PWM11_18") (pintype "output"))
    )
    (net (code "91") (name "M12_POT") (class "Default")
      (node (ref "MOD_12") (pin "7") (pinfunction "7_7") (pintype "passive"))
      (node (ref "POTS") (pin "20") (pinfunction "CHAN11_20") (pintype "bidirectional"))
    )
    (net (code "92") (name "M12_X") (class "Default")
      (node (ref "MOD_12") (pin "6") (pinfunction "6_6") (pintype "passive"))
      (node (ref "X") (pin "20") (pinfunction "CHAN11_20") (pintype "bidirectional"))
    )
    (net (code "93") (name "M12_Y") (class "Default")
      (node (ref "MOD_12") (pin "5") (pinfunction "5_5") (pintype "passive"))
      (node (ref "Y") (pin "20") (pinfunction "CHAN11_20") (pintype "bidirectional"))
    )
    (net (code "94") (name "M13_BTN") (class "Default")
      (node (ref "BUTTONS") (pin "19") (pinfunction "CHAN12_19") (pintype "bidirectional"))
      (node (ref "MOD_13") (pin "4") (pinfunction "4_4") (pintype "passive"))
    )
    (net (code "95") (name "M13_LED1") (class "Default")
      (node (ref "BLUE_DRIVER") (pin "19") (pinfunction "PWM12_19") (pintype "output"))
      (node (ref "MOD_13") (pin "2") (pinfunction "2_2") (pintype "passive"))
    )
    (net (code "96") (name "M13_LED2") (class "Default")
      (node (ref "MOD_13") (pin "3") (pinfunction "3_3") (pintype "passive"))
      (node (ref "ORANGE_DRIVER") (pin "19") (pinfunction "PWM12_19") (pintype "output"))
    )
    (net (code "97") (name "M13_POT") (class "Default")
      (node (ref "MOD_13") (pin "7") (pinfunction "7_7") (pintype "passive"))
      (node (ref "POTS") (pin "19") (pinfunction "CHAN12_19") (pintype "bidirectional"))
    )
    (net (code "98") (name "M13_X") (class "Default")
      (node (ref "MOD_13") (pin "6") (pinfunction "6_6") (pintype "passive"))
      (node (ref "X") (pin "19") (pinfunction "CHAN12_19") (pintype "bidirectional"))
    )
    (net (code "99") (name "M13_Y") (class "Default")
      (node (ref "MOD_13") (pin "5") (pinfunction "5_5") (pintype "passive"))
      (node (ref "Y") (pin "19") (pinfunction "CHAN12_19") (pintype "bidirectional"))
    )
    (net (code "100") (name "M14_BTN") (class "Default")
      (node (ref "BUTTONS") (pin "18") (pinfunction "CHAN13_18") (pintype "bidirectional"))
      (node (ref "MOD_14") (pin "4") (pinfunction "4_4") (pintype "passive"))
    )
    (net (code "101") (name "M14_LED1") (class "Default")
      (node (ref "BLUE_DRIVER") (pin "20") (pinfunction "PWM13_20") (pintype "output"))
      (node (ref "MOD_14") (pin "2") (pinfunction "2_2") (pintype "passive"))
    )
    (net (code "102") (name "M14_LED2") (class "Default")
      (node (ref "MOD_14") (pin "3") (pinfunction "3_3") (pintype "passive"))
      (node (ref "ORANGE_DRIVER") (pin "20") (pinfunction "PWM13_20") (pintype "output"))
    )
    (net (code "103") (name "M14_POT") (class "Default")
      (node (ref "MOD_14") (pin "7") (pinfunction "7_7") (pintype "passive"))
      (node (ref "POTS") (pin "18") (pinfunction "CHAN13_18") (pintype "bidirectional"))
    )
    (net (code "104") (name "M14_X") (class "Default")
      (node (ref "MOD_14") (pin "6") (pinfunction "6_6") (pintype "passive"))
      (node (ref "X") (pin "18") (pinfunction "CHAN13_18") (pintype "bidirectional"))
    )
    (net (code "105") (name "M14_Y") (class "Default")
      (node (ref "MOD_14") (pin "5") (pinfunction "5_5") (pintype "passive"))
      (node (ref "Y") (pin "18") (pinfunction "CHAN13_18") (pintype "bidirectional"))
    )
    (net (code "106") (name "M15_BTN") (class "Default")
      (node (ref "BUTTONS") (pin "17") (pinfunction "CHAN14_17") (pintype "bidirectional"))
      (node (ref "MOD_15") (pin "4") (pinfunction "4_4") (pintype "passive"))
    )
    (net (code "107") (name "M15_LED1") (class "Default")
      (node (ref "BLUE_DRIVER") (pin "21") (pinfunction "PWM14_21") (pintype "output"))
      (node (ref "MOD_15") (pin "2") (pinfunction "2_2") (pintype "passive"))
    )
    (net (code "108") (name "M15_LED2") (class "Default")
      (node (ref "MOD_15") (pin "3") (pinfunction "3_3") (pintype "passive"))
      (node (ref "ORANGE_DRIVER") (pin "21") (pinfunction "PWM14_21") (pintype "output"))
    )
    (net (code "109") (name "M15_POT") (class "Default")
      (node (ref "MOD_15") (pin "7") (pinfunction "7_7") (pintype "passive"))
      (node (ref "POTS") (pin "17") (pinfunction "CHAN14_17") (pintype "bidirectional"))
    )
    (net (code "110") (name "M15_X") (class "Default")
      (node (ref "MOD_15") (pin "6") (pinfunction "6_6") (pintype "passive"))
      (node (ref "X") (pin "17") (pinfunction "CHAN14_17") (pintype "bidirectional"))
    )
    (net (code "111") (name "M15_Y") (class "Default")
      (node (ref "MOD_15") (pin "5") (pinfunction "5_5") (pintype "passive"))
      (node (ref "Y") (pin "17") (pinfunction "CHAN14_17") (pintype "bidirectional"))
    )
    (net (code "112") (name "M16_BTN") (class "Default")
      (node (ref "BUTTONS") (pin "16") (pinfunction "CHAN15_16") (pintype "bidirectional"))
      (node (ref "MOD_16") (pin "4") (pinfunction "4_4") (pintype "passive"))
    )
    (net (code "113") (name "M16_LED1") (class "Default")
      (node (ref "BLUE_DRIVER") (pin "22") (pinfunction "PWM15_22") (pintype "output"))
      (node (ref "MOD_16") (pin "2") (pinfunction "2_2") (pintype "passive"))
    )
    (net (code "114") (name "M16_LED2") (class "Default")
      (node (ref "MOD_16") (pin "3") (pinfunction "3_3") (pintype "passive"))
      (node (ref "ORANGE_DRIVER") (pin "22") (pinfunction "PWM15_22") (pintype "output"))
    )
    (net (code "115") (name "M16_POT") (class "Default")
      (node (ref "MOD_16") (pin "7") (pinfunction "7_7") (pintype "passive"))
      (node (ref "POTS") (pin "16") (pinfunction "CHAN15_16") (pintype "bidirectional"))
    )
    (net (code "116") (name "M16_X") (class "Default")
      (node (ref "MOD_16") (pin "6") (pinfunction "6_6") (pintype "passive"))
      (node (ref "X") (pin "16") (pinfunction "CHAN15_16") (pintype "bidirectional"))
    )
    (net (code "117") (name "M16_Y") (class "Default")
      (node (ref "MOD_16") (pin "5") (pinfunction "5_5") (pintype "passive"))
      (node (ref "Y") (pin "16") (pinfunction "CHAN15_16") (pintype "bidirectional"))
    )
    (net (code "118") (name "MUX1_S0") (class "Default")
      (node (ref "POTS") (pin "10") (pinfunction "S0_10") (pintype "input"))
      (node (ref "TEENSY++") (pin "D7") (pinfunction "7_D7") (pintype "bidirectional"))
    )
    (net (code "119") (name "MUX1_S1") (class "Default")
      (node (ref "POTS") (pin "11") (pinfunction "S1_11") (pintype "input"))
      (node (ref "TEENSY++") (pin "D6") (pinfunction "6,LED_D6") (pintype "bidirectional"))
    )
    (net (code "120") (name "MUX1_S2") (class "Default")
      (node (ref "POTS") (pin "14") (pinfunction "S2_14") (pintype "input"))
      (node (ref "TEENSY++") (pin "D5") (pinfunction "5_D5") (pintype "bidirectional"))
    )
    (net (code "121") (name "MUX1_S3") (class "Default")
      (node (ref "POTS") (pin "13") (pinfunction "S3_13") (pintype "input"))
      (node (ref "TEENSY++") (pin "D4") (pinfunction "4_D4") (pintype "bidirectional"))
    )
    (net (code "122") (name "MUX1_SIG") (class "Default")
      (node (ref "POTS") (pin "1") (pinfunction "COM_1") (pintype "bidirectional"))
      (node (ref "TEENSY++") (pin "F1") (pinfunction "39,A1_F1") (pintype "bidirectional"))
    )
    (net (code "123") (name "MUX2_S0") (class "Default")
      (node (ref "TEENSY++") (pin "C1") (pinfunction "11_C1") (pintype "bidirectional"))
      (node (ref "X") (pin "10") (pinfunction "S0_10") (pintype "input"))
    )
    (net (code "124") (name "MUX2_S1") (class "Default")
      (node (ref "TEENSY++") (pin "C0") (pinfunction "10_C0") (pintype "bidirectional"))
      (node (ref "X") (pin "11") (pinfunction "S1_11") (pintype "input"))
    )
    (net (code "125") (name "MUX2_S2") (class "Default")
      (node (ref "TEENSY++") (pin "E1") (pinfunction "9_E1") (pintype "bidirectional"))
      (node (ref "X") (pin "14") (pinfunction "S2_14") (pintype "input"))
    )
    (net (code "126") (name "MUX2_S3") (class "Default")
      (node (ref "TEENSY++") (pin "E0") (pinfunction "8_E0") (pintype "bidirectional"))
      (node (ref "X") (pin "13") (pinfunction "S3_13") (pintype "input"))
    )
    (net (code "127") (name "MUX2_SIG") (class "Default")
      (node (ref "TEENSY++") (pin "F2") (pinfunction "40,A2_F2") (pintype "bidirectional"))
      (node (ref "X") (pin "1") (pinfunction "COM_1") (pintype "bidirectional"))
    )
    (net (code "128") (name "MUX3_S0") (class "Default")
      (node (ref "TEENSY++") (pin "C5") (pinfunction "15,PWM_C5") (pintype "bidirectional"))
      (node (ref "Y") (pin "10") (pinfunction "S0_10") (pintype "input"))
    )
    (net (code "129") (name "MUX3_S1") (class "Default")
      (node (ref "TEENSY++") (pin "C4") (pinfunction "14,PWM_C4") (pintype "bidirectional"))
      (node (ref "Y") (pin "11") (pinfunction "S1_11") (pintype "input"))
    )
    (net (code "130") (name "MUX3_S2") (class "Default")
      (node (ref "TEENSY++") (pin "C3") (pinfunction "13_C3") (pintype "bidirectional"))
      (node (ref "Y") (pin "14") (pinfunction "S2_14") (pintype "input"))
    )
    (net (code "131") (name "MUX3_S3") (class "Default")
      (node (ref "TEENSY++") (pin "C2") (pinfunction "12_C2") (pintype "bidirectional"))
      (node (ref "Y") (pin "13") (pinfunction "S3_13") (pintype "input"))
    )
    (net (code "132") (name "MUX3_SIG") (class "Default")
      (node (ref "TEENSY++") (pin "F3") (pinfunction "41,A3_F3") (pintype "bidirectional"))
      (node (ref "Y") (pin "1") (pinfunction "COM_1") (pintype "bidirectional"))
    )
    (net (code "133") (name "MUX4_S0") (class "Default")
      (node (ref "BUTTONS") (pin "10") (pinfunction "S0_10") (pintype "input"))
      (node (ref "TEENSY++") (pin "B3") (pinfunction "23_B3") (pintype "bidirectional"))
    )
    (net (code "134") (name "MUX4_S1") (class "Default")
      (node (ref "BUTTONS") (pin "11") (pinfunction "S1_11") (pintype "input"))
      (node (ref "TEENSY++") (pin "B2") (pinfunction "22_B2") (pintype "bidirectional"))
    )
    (net (code "135") (name "MUX4_S2") (class "Default")
      (node (ref "BUTTONS") (pin "14") (pinfunction "S2_14") (pintype "input"))
      (node (ref "TEENSY++") (pin "B1") (pinfunction "21_B1") (pintype "bidirectional"))
    )
    (net (code "136") (name "MUX4_S3") (class "Default")
      (node (ref "BUTTONS") (pin "13") (pinfunction "S3_13") (pintype "input"))
      (node (ref "TEENSY++") (pin "B0") (pinfunction "20_B0") (pintype "bidirectional"))
    )
    (net (code "137") (name "MUX4_SIG") (class "Default")
      (node (ref "BUTTONS") (pin "1") (pinfunction "COM_1") (pintype "bidirectional"))
      (node (ref "TEENSY++") (pin "F4") (pinfunction "42,A4_F4") (pintype "bidirectional"))
    )
    (net (code "138") (name "Net-(LED1-PadC)") (class "Default")
      (node (ref "LED1") (pin "C") (pinfunction "C_C") (pintype "passive"))
      (node (ref "R12") (pin "1") (pinfunction "1_1") (pintype "passive"))
    )
    (net (code "139") (name "Net-(Q1-D)") (class "Default")
      (node (ref "J2") (pin "PWR") (pinfunction "PWR_PWR") (pintype "bidirectional"))
      (node (ref "Q1") (pin "3") (pinfunction "D_3") (pintype "passive"))
    )
    (net (code "140") (name "SCL") (class "Default")
      (node (ref "BLUE_DRIVER") (pin "26") (pinfunction "SCL_26") (pintype "bidirectional"))
      (node (ref "I2C") (pin "2") (pinfunction "2_2") (pintype "passive"))
      (node (ref "ORANGE_DRIVER") (pin "26") (pinfunction "SCL_26") (pintype "bidirectional"))
      (node (ref "R1") (pin "P$1") (pinfunction "1_P$1") (pintype "passive"))
      (node (ref "R11") (pin "1") (pinfunction "1_1") (pintype "passive"))
      (node (ref "R37") (pin "1") (pinfunction "1_1") (pintype "passive"))
      (node (ref "TEENSY++") (pin "D0") (pinfunction "0,PWM,INT0_D0") (pintype "bidirectional"))
    )
    (net (code "141") (name "SDA") (class "Default")
      (node (ref "BLUE_DRIVER") (pin "27") (pinfunction "SDA_27") (pintype "bidirectional"))
      (node (ref "I2C") (pin "1") (pinfunction "1_1") (pintype "passive"))
      (node (ref "ORANGE_DRIVER") (pin "27") (pinfunction "SDA_27") (pintype "bidirectional"))
      (node (ref "R10") (pin "1") (pinfunction "1_1") (pintype "passive"))
      (node (ref "R2") (pin "P$2") (pinfunction "2_P$2") (pintype "passive"))
      (node (ref "R36") (pin "1") (pinfunction "1_1") (pintype "passive"))
      (node (ref "TEENSY++") (pin "D1") (pinfunction "1,PWM,INT1_D1") (pintype "bidirectional"))
    )
    (net (code "142") (name "unconnected-(TEENSY++-2,RX,INT2-PadD2)") (class "Default")
      (node (ref "TEENSY++") (pin "D2") (pinfunction "2,RX,INT2_D2") (pintype "bidirectional"))
    )
    (net (code "143") (name "unconnected-(TEENSY++-3,TX,INT3-PadD3)") (class "Default")
      (node (ref "TEENSY++") (pin "D3") (pinfunction "3,TX,INT3_D3") (pintype "bidirectional"))
    )
    (net (code "144") (name "unconnected-(TEENSY++-16,PWM-PadC6)") (class "Default")
      (node (ref "TEENSY++") (pin "C6") (pinfunction "16,PWM_C6") (pintype "bidirectional"))
    )
    (net (code "145") (name "unconnected-(TEENSY++-18,INT6-PadE6)") (class "Default")
      (node (ref "TEENSY++") (pin "E6") (pinfunction "18,INT6_E6") (pintype "bidirectional"))
    )
    (net (code "146") (name "unconnected-(TEENSY++-19-PadE7)") (class "Default")
      (node (ref "TEENSY++") (pin "E7") (pinfunction "19_E7") (pintype "bidirectional"))
    )
    (net (code "147") (name "unconnected-(TEENSY++-24,PWM-PadB4)") (class "Default")
      (node (ref "TEENSY++") (pin "B4") (pinfunction "24,PWM_B4") (pintype "bidirectional"))
    )
    (net (code "148") (name "unconnected-(TEENSY++-27,PWM-PadB7)") (class "Default")
      (node (ref "TEENSY++") (pin "B7") (pinfunction "27,PWM_B7") (pintype "bidirectional"))
    )
    (net (code "149") (name "unconnected-(TEENSY++-28-PadA0)") (class "Default")
      (node (ref "TEENSY++") (pin "A0") (pinfunction "28_A0") (pintype "bidirectional"))
    )
    (net (code "150") (name "unconnected-(TEENSY++-29-PadA1)") (class "Default")
      (node (ref "TEENSY++") (pin "A1") (pinfunction "29_A1") (pintype "bidirectional"))
    )
    (net (code "151") (name "unconnected-(TEENSY++-30-PadA2)") (class "Default")
      (node (ref "TEENSY++") (pin "A2") (pinfunction "30_A2") (pintype "bidirectional"))
    )
    (net (code "152") (name "unconnected-(TEENSY++-31-PadA3)") (class "Default")
      (node (ref "TEENSY++") (pin "A3") (pinfunction "31_A3") (pintype "bidirectional"))
    )
    (net (code "153") (name "unconnected-(TEENSY++-32-PadA4)") (class "Default")
      (node (ref "TEENSY++") (pin "A4") (pinfunction "32_A4") (pintype "bidirectional"))
    )
    (net (code "154") (name "unconnected-(TEENSY++-33-PadA5)") (class "Default")
      (node (ref "TEENSY++") (pin "A5") (pinfunction "33_A5") (pintype "bidirectional"))
    )
    (net (code "155") (name "unconnected-(TEENSY++-34-PadA6)") (class "Default")
      (node (ref "TEENSY++") (pin "A6") (pinfunction "34_A6") (pintype "bidirectional"))
    )
    (net (code "156") (name "unconnected-(TEENSY++-35-PadA7)") (class "Default")
      (node (ref "TEENSY++") (pin "A7") (pinfunction "35_A7") (pintype "bidirectional"))
    )
    (net (code "157") (name "unconnected-(TEENSY++-38,A0-PadF0)") (class "Default")
      (node (ref "TEENSY++") (pin "F0") (pinfunction "38,A0_F0") (pintype "bidirectional"))
    )
    (net (code "158") (name "unconnected-(TEENSY++-43,A5-PadF5)") (class "Default")
      (node (ref "TEENSY++") (pin "F5") (pinfunction "43,A5_F5") (pintype "bidirectional"))
    )
    (net (code "159") (name "unconnected-(TEENSY++-44,A6-PadF6)") (class "Default")
      (node (ref "TEENSY++") (pin "F6") (pinfunction "44,A6_F6") (pintype "bidirectional"))
    )
    (net (code "160") (name "unconnected-(TEENSY++-45,A7-PadF7)") (class "Default")
      (node (ref "TEENSY++") (pin "F7") (pinfunction "45,A7_F7") (pintype "bidirectional"))
    )
    (net (code "161") (name "unconnected-(TEENSY++-AREF-PadREF)") (class "Default")
      (node (ref "TEENSY++") (pin "REF") (pinfunction "AREF_REF") (pintype "input"))
    )
    (net (code "162") (name "unconnected-(TEENSY++-_RST-PadRST)") (class "Default")
      (node (ref "TEENSY++") (pin "RST") (pinfunction "_RST_RST") (pintype "input"))
    )
  )
)
